# LCD.net
KiCad netlist of a schematic drawn in Altium Designer
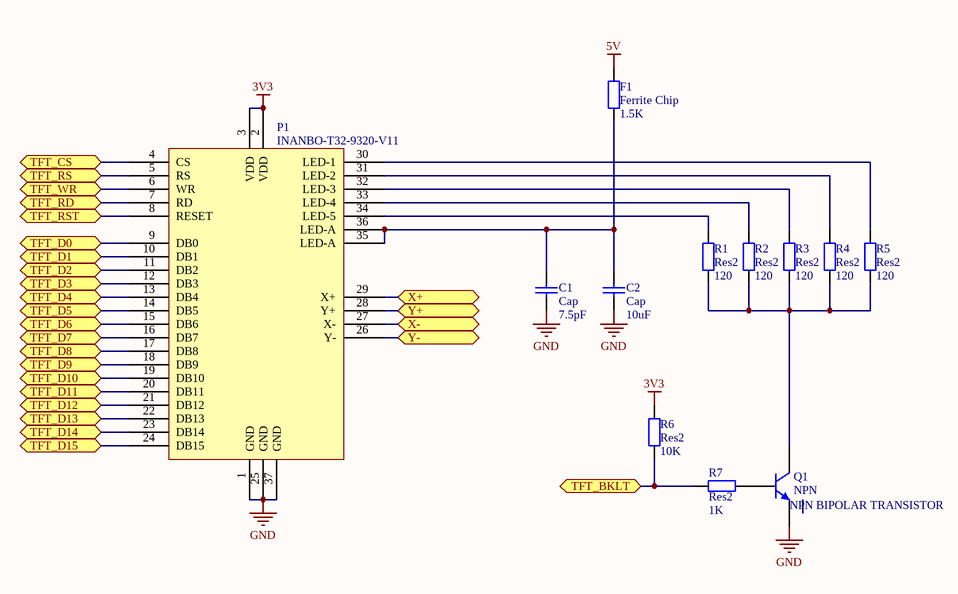
[diagram p0: LCD.SchDoc]

(export (version "E")
  (design (tool "Eeschema 10.0.6"))
  (components
    (comp (ref "C1")
      (value "Cap")
      (footprint "0603")
      (description "Capacitor")
      (fields (field (name "ALTIUM_VALUE") "7.5pF"))
      (libsource (lib "Miscellaneous Devices") (part "Cap"))
    )
    (comp (ref "C2")
      (value "Cap")
      (footprint "0805")
      (description "Capacitor")
      (fields (field (name "ALTIUM_VALUE") "10uF"))
      (libsource (lib "Miscellaneous Devices") (part "Cap"))
    )
    (comp (ref "F1")
      (value "Ferrite Chip")
      (footprint "0603")
      (fields (field (name "ALTIUM_VALUE") "1.5K"))
      (libsource (lib "") (part "Res2_2"))
    )
    (comp (ref "P1")
      (value "INANBO-T32-9320-V11")
      (footprint "INANBO-T32-ILI9320-V11")
      (description "3.2\" TFT LCD module with touch panel")
      (libsource (lib "BrewBit") (part "ER-TFT032-2"))
    )
    (comp (ref "Q1")
      (value "NPN")
      (footprint "SOT23_M")
      (description "NPN Bipolar Transistor")
      (fields (field (name "ALTIUM_VALUE") "NPN BIPOLAR TRANSISTOR"))
      (libsource (lib "Miscellaneous Devices") (part "NPN"))
    )
    (comp (ref "R1")
      (value "Res2")
      (footprint "0603")
      (description "Resistor")
      (fields (field (name "ALTIUM_VALUE") "120"))
      (libsource (lib "Miscellaneous Devices") (part "Res2"))
    )
    (comp (ref "R2")
      (value "Res2")
      (footprint "0603")
      (description "Resistor")
      (fields (field (name "ALTIUM_VALUE") "120"))
      (libsource (lib "Miscellaneous Devices") (part "Res2"))
    )
    (comp (ref "R3")
      (value "Res2")
      (footprint "0603")
      (description "Resistor")
      (fields (field (name "ALTIUM_VALUE") "120"))
      (libsource (lib "Miscellaneous Devices") (part "Res2"))
    )
    (comp (ref "R4")
      (value "Res2")
      (footprint "0603")
      (description "Resistor")
      (fields (field (name "ALTIUM_VALUE") "120"))
      (libsource (lib "Miscellaneous Devices") (part "Res2"))
    )
    (comp (ref "R5")
      (value "Res2")
      (footprint "0603")
      (description "Resistor")
      (fields (field (name "ALTIUM_VALUE") "120"))
      (libsource (lib "Miscellaneous Devices") (part "Res2"))
    )
    (comp (ref "R6")
      (value "Res2")
      (footprint "0603")
      (description "Resistor")
      (fields (field (name "ALTIUM_VALUE") "10K"))
      (libsource (lib "Miscellaneous Devices") (part "Res2"))
    )
    (comp (ref "R7")
      (value "Res2")
      (footprint "0603")
      (description "Resistor")
      (fields (field (name "ALTIUM_VALUE") "1K"))
      (libsource (lib "") (part "Res2_1"))
    )
  )
  (nets
    (net (code "1") (name "/TFT_BKLT") (class "Default")
      (node (ref "R6") (pin "1") (pinfunction "1_1") (pintype "passive"))
      (node (ref "R7") (pin "2") (pinfunction "2_2") (pintype "passive"))
    )
    (net (code "2") (name "/TFT_CS") (class "Default")
      (node (ref "P1") (pin "4") (pinfunction "CS_4") (pintype "passive"))
    )
    (net (code "3") (name "/TFT_D0") (class "Default")
      (node (ref "P1") (pin "9") (pinfunction "DB0_9") (pintype "passive"))
    )
    (net (code "4") (name "/TFT_D1") (class "Default")
      (node (ref "P1") (pin "10") (pinfunction "DB1_10") (pintype "passive"))
    )
    (net (code "5") (name "/TFT_D2") (class "Default")
      (node (ref "P1") (pin "11") (pinfunction "DB2_11") (pintype "passive"))
    )
    (net (code "6") (name "/TFT_D3") (class "Default")
      (node (ref "P1") (pin "12") (pinfunction "DB3_12") (pintype "passive"))
    )
    (net (code "7") (name "/TFT_D4") (class "Default")
      (node (ref "P1") (pin "13") (pinfunction "DB4_13") (pintype "passive"))
    )
    (net (code "8") (name "/TFT_D5") (class "Default")
      (node (ref "P1") (pin "14") (pinfunction "DB5_14") (pintype "passive"))
    )
    (net (code "9") (name "/TFT_D6") (class "Default")
      (node (ref "P1") (pin "15") (pinfunction "DB6_15") (pintype "passive"))
    )
    (net (code "10") (name "/TFT_D7") (class "Default")
      (node (ref "P1") (pin "16") (pinfunction "DB7_16") (pintype "passive"))
    )
    (net (code "11") (name "/TFT_D8") (class "Default")
      (node (ref "P1") (pin "17") (pinfunction "DB8_17") (pintype "passive"))
    )
    (net (code "12") (name "/TFT_D9") (class "Default")
      (node (ref "P1") (pin "18") (pinfunction "DB9_18") (pintype "passive"))
    )
    (net (code "13") (name "/TFT_D10") (class "Default")
      (node (ref "P1") (pin "19") (pinfunction "DB10_19") (pintype "passive"))
    )
    (net (code "14") (name "/TFT_D11") (class "Default")
      (node (ref "P1") (pin "20") (pinfunction "DB11_20") (pintype "passive"))
    )
    (net (code "15") (name "/TFT_D12") (class "Default")
      (node (ref "P1") (pin "21") (pinfunction "DB12_21") (pintype "passive"))
    )
    (net (code "16") (name "/TFT_D13") (class "Default")
      (node (ref "P1") (pin "22") (pinfunction "DB13_22") (pintype "passive"))
    )
    (net (code "17") (name "/TFT_D14") (class "Default")
      (node (ref "P1") (pin "23") (pinfunction "DB14_23") (pintype "passive"))
    )
    (net (code "18") (name "/TFT_D15") (class "Default")
      (node (ref "P1") (pin "24") (pinfunction "DB15_24") (pintype "passive"))
    )
    (net (code "19") (name "/TFT_RD") (class "Default")
      (node (ref "P1") (pin "7") (pinfunction "RD_7") (pintype "passive"))
    )
    (net (code "20") (name "/TFT_RS") (class "Default")
      (node (ref "P1") (pin "5") (pinfunction "RS_5") (pintype "passive"))
    )
    (net (code "21") (name "/TFT_RST") (class "Default")
      (node (ref "P1") (pin "8") (pinfunction "RESET_8") (pintype "passive"))
    )
    (net (code "22") (name "/TFT_WR") (class "Default")
      (node (ref "P1") (pin "6") (pinfunction "WR_6") (pintype "passive"))
    )
    (net (code "23") (name "/X+") (class "Default")
      (node (ref "P1") (pin "29") (pinfunction "X+_29") (pintype "passive"))
    )
    (net (code "24") (name "/X-") (class "Default")
      (node (ref "P1") (pin "27") (pinfunction "X-_27") (pintype "passive"))
    )
    (net (code "25") (name "/Y+") (class "Default")
      (node (ref "P1") (pin "28") (pinfunction "Y+_28") (pintype "passive"))
    )
    (net (code "26") (name "/Y-") (class "Default")
      (node (ref "P1") (pin "26") (pinfunction "Y-_26") (pintype "passive"))
    )
    (net (code "27") (name "3V3") (class "Default")
      (node (ref "P1") (pin "2") (pinfunction "VDD_2") (pintype "passive"))
      (node (ref "P1") (pin "3") (pinfunction "VDD_3") (pintype "passive"))
      (node (ref "R6") (pin "2") (pinfunction "2_2") (pintype "passive"))
    )
    (net (code "28") (name "5V") (class "Default")
      (node (ref "F1") (pin "1") (pinfunction "1_1") (pintype "passive"))
    )
    (net (code "29") (name "GND") (class "Default")
      (node (ref "C1") (pin "1") (pinfunction "1_1") (pintype "passive"))
      (node (ref "C2") (pin "1") (pinfunction "1_1") (pintype "passive"))
      (node (ref "P1") (pin "1") (pinfunction "GND_1") (pintype "passive"))
      (node (ref "P1") (pin "25") (pinfunction "GND_25") (pintype "passive"))
      (node (ref "P1") (pin "37") (pinfunction "GND_37") (pintype "passive"))
      (node (ref "Q1") (pin "3") (pinfunction "E_3") (pintype "passive"))
    )
    (net (code "30") (name "Net-(C1-Pad2)") (class "Default")
      (node (ref "C1") (pin "2") (pinfunction "2_2") (pintype "passive"))
      (node (ref "C2") (pin "2") (pinfunction "2_2") (pintype "passive"))
      (node (ref "F1") (pin "2") (pinfunction "2_2") (pintype "passive"))
      (node (ref "P1") (pin "35") (pinfunction "LED-A_35") (pintype "passive"))
      (node (ref "P1") (pin "36") (pinfunction "LED-A_36") (pintype "passive"))
    )
    (net (code "31") (name "Net-(P1-LED-1)") (class "Default")
      (node (ref "P1") (pin "30") (pinfunction "LED-1_30") (pintype "passive"))
      (node (ref "R5") (pin "2") (pinfunction "2_2") (pintype "passive"))
    )
    (net (code "32") (name "Net-(P1-LED-2)") (class "Default")
      (node (ref "P1") (pin "31") (pinfunction "LED-2_31") (pintype "passive"))
      (node (ref "R4") (pin "2") (pinfunction "2_2") (pintype "passive"))
    )
    (net (code "33") (name "Net-(P1-LED-3)") (class "Default")
      (node (ref "P1") (pin "32") (pinfunction "LED-3_32") (pintype "passive"))
      (node (ref "R3") (pin "2") (pinfunction "2_2") (pintype "passive"))
    )
    (net (code "34") (name "Net-(P1-LED-4)") (class "Default")
      (node (ref "P1") (pin "33") (pinfunction "LED-4_33") (pintype "passive"))
      (node (ref "R2") (pin "2") (pinfunction "2_2") (pintype "passive"))
    )
    (net (code "35") (name "Net-(P1-LED-5)") (class "Default")
      (node (ref "P1") (pin "34") (pinfunction "LED-5_34") (pintype "passive"))
      (node (ref "R1") (pin "2") (pinfunction "2_2") (pintype "passive"))
    )
    (net (code "36") (name "Net-(Q1-B)") (class "Default")
      (node (ref "Q1") (pin "2") (pinfunction "B_2") (pintype "passive"))
      (node (ref "R7") (pin "1") (pinfunction "1_1") (pintype "passive"))
    )
    (net (code "37") (name "Net-(Q1-C)") (class "Default")
      (node (ref "Q1") (pin "1") (pinfunction "C_1") (pintype "passive"))
      (node (ref "R1") (pin "1") (pinfunction "1_1") (pintype "passive"))
      (node (ref "R2") (pin "1") (pinfunction "1_1") (pintype "passive"))
      (node (ref "R3") (pin "1") (pinfunction "1_1") (pintype "passive"))
      (node (ref "R4") (pin "1") (pinfunction "1_1") (pintype "passive"))
      (node (ref "R5") (pin "1") (pinfunction "1_1") (pintype "passive"))
    )
  )
)
